# sch_cm4.net
KiCad netlist of a schematic drawn in Altium Designer
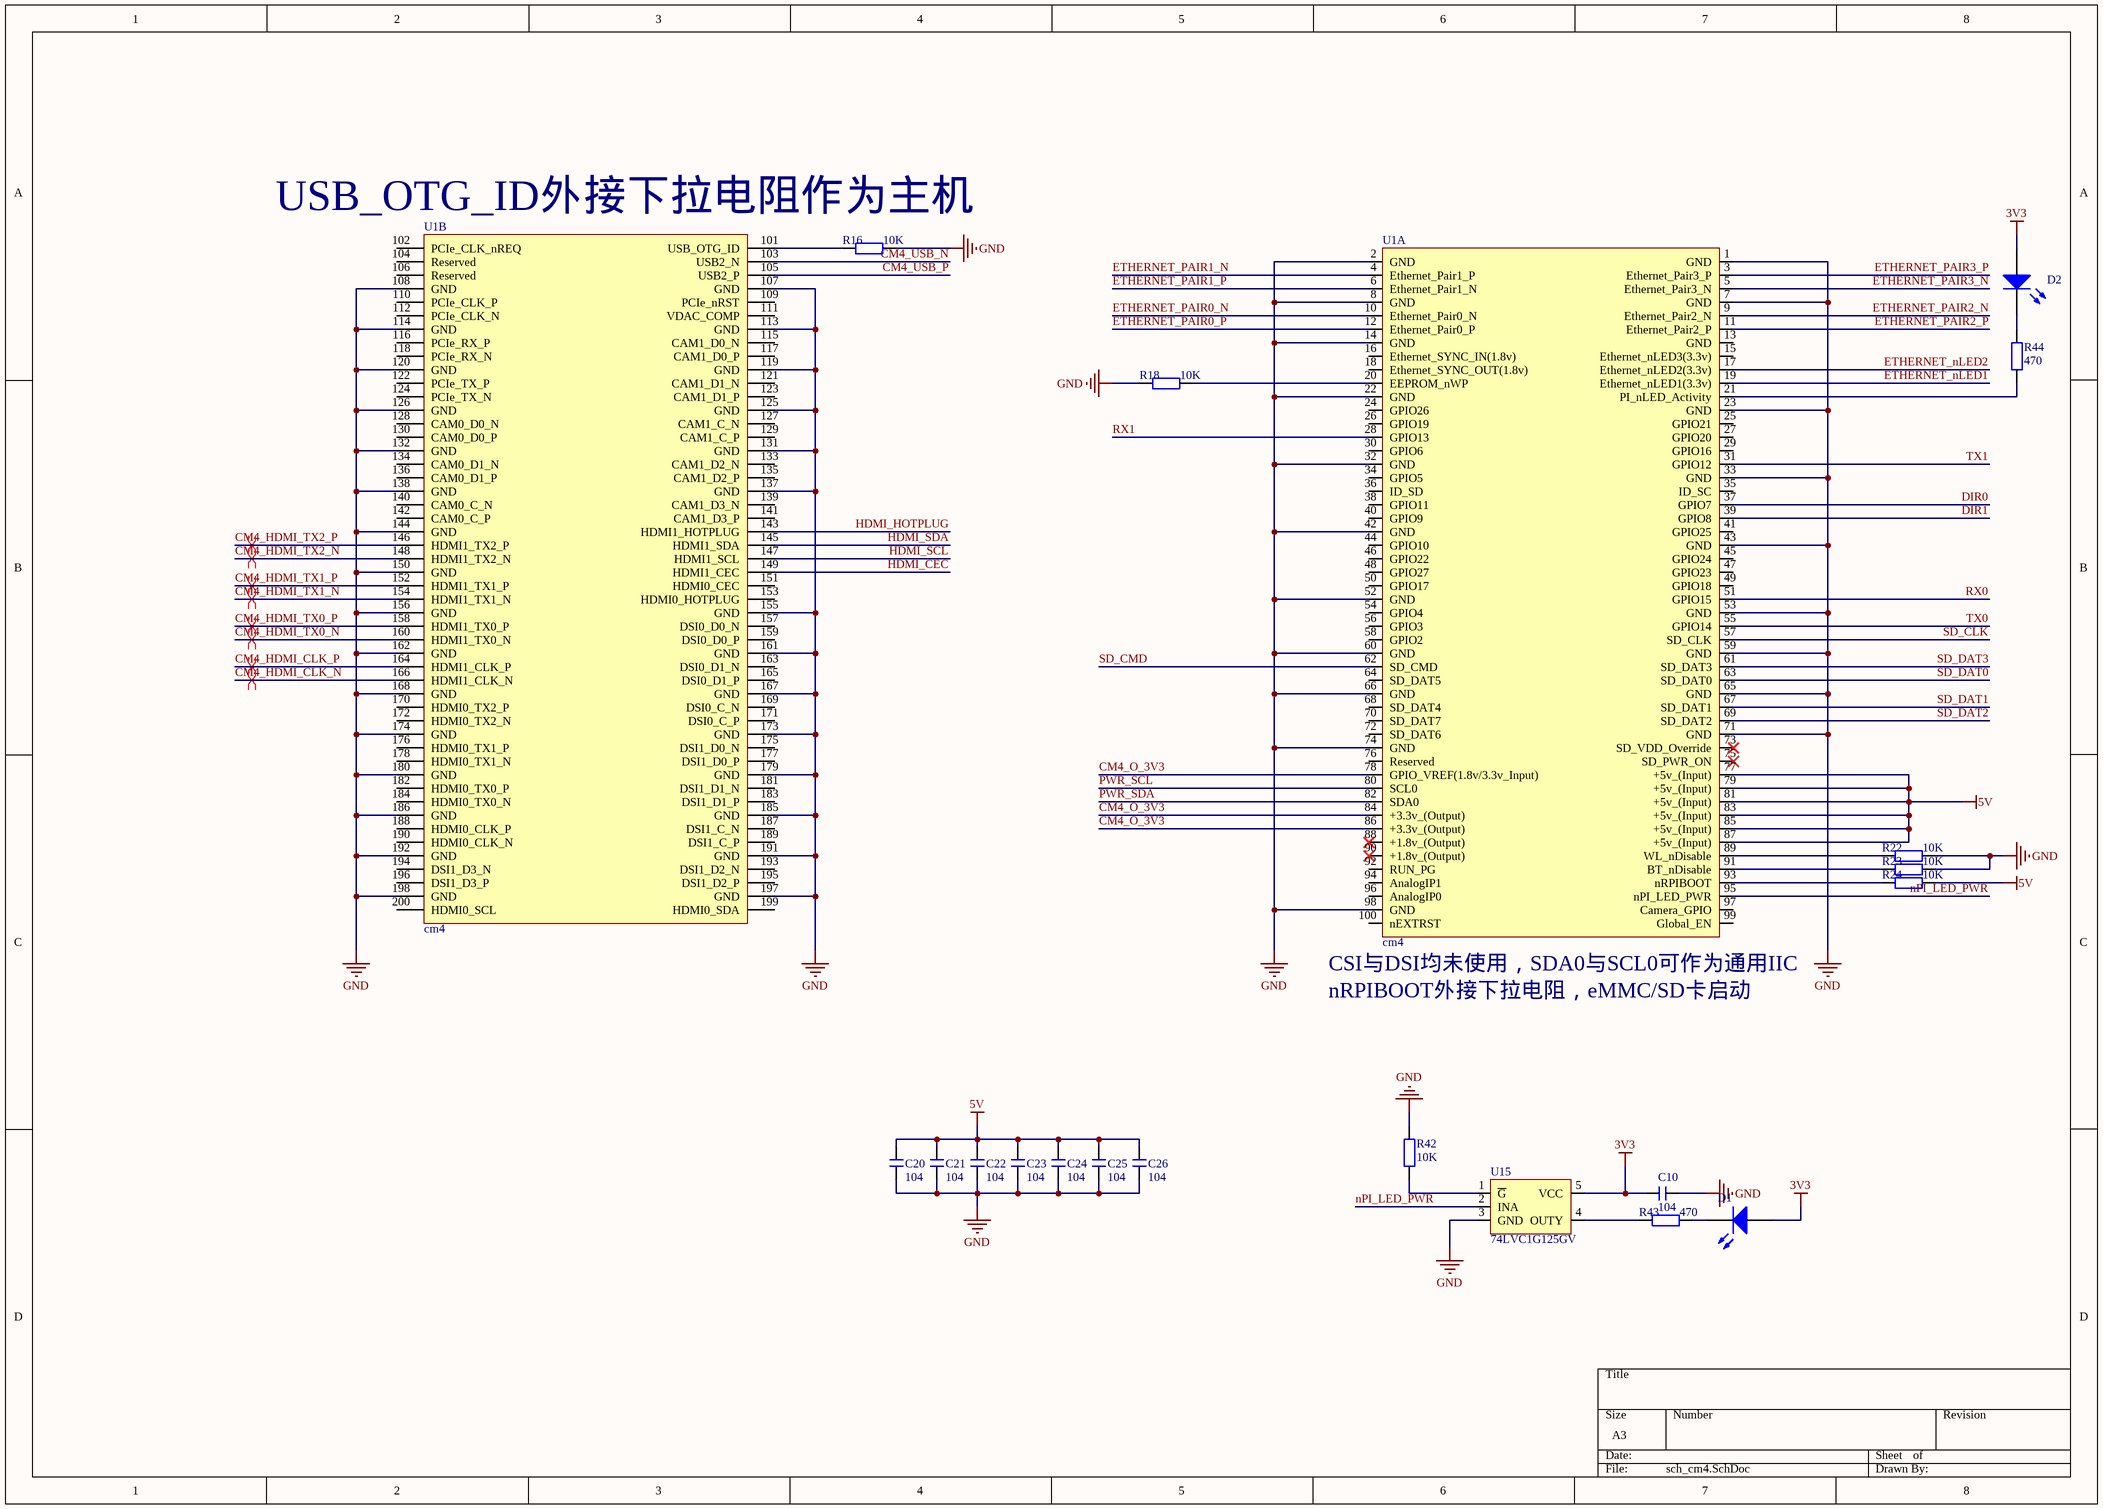
[diagram p0: sch_cm4.SchDoc]

(export (version "E")
  (design (tool "Eeschema 10.0.6"))
  (components
    (comp (ref "C10")
      (value "104")
      (footprint "C 0402_L")
      (description "贴片电容")
      (libsource (lib "0.1 - 电阻-电容-电感") (part "C"))
    )
    (comp (ref "C20")
      (value "104")
      (footprint "C 0402_L")
      (description "贴片电容")
      (libsource (lib "0.1 - 电阻-电容-电感") (part "C"))
    )
    (comp (ref "C21")
      (value "104")
      (footprint "C 0402_L")
      (description "贴片电容")
      (libsource (lib "0.1 - 电阻-电容-电感") (part "C"))
    )
    (comp (ref "C22")
      (value "104")
      (footprint "C 0402_L")
      (description "贴片电容")
      (libsource (lib "0.1 - 电阻-电容-电感") (part "C"))
    )
    (comp (ref "C23")
      (value "104")
      (footprint "C 0402_L")
      (description "贴片电容")
      (libsource (lib "0.1 - 电阻-电容-电感") (part "C"))
    )
    (comp (ref "C24")
      (value "104")
      (footprint "C 0402_L")
      (description "贴片电容")
      (libsource (lib "0.1 - 电阻-电容-电感") (part "C"))
    )
    (comp (ref "C25")
      (value "104")
      (footprint "C 0402_L")
      (description "贴片电容")
      (libsource (lib "0.1 - 电阻-电容-电感") (part "C"))
    )
    (comp (ref "C26")
      (value "104")
      (footprint "C 0402_L")
      (description "贴片电容")
      (libsource (lib "0.1 - 电阻-电容-电感") (part "C"))
    )
    (comp (ref "D1")
      (value "Light-Emitting Diode")
      (libsource (lib "Simulation Generic Components") (part "LED"))
    )
    (comp (ref "D2")
      (value "Light-Emitting Diode")
      (libsource (lib "Simulation Generic Components") (part "LED"))
    )
    (comp (ref "R16")
      (value "10K")
      (footprint "R 0805_L")
      (description "贴片电阻")
      (fields (field (name "版权归属") "来自淘宝 ID：黄晶宝石"))
      (libsource (lib "0.1 - 电阻-电容-电感") (part "R"))
    )
    (comp (ref "R18")
      (value "10K")
      (footprint "R 0805_L")
      (description "贴片电阻")
      (fields (field (name "版权归属") "来自淘宝 ID：黄晶宝石"))
      (libsource (lib "0.1 - 电阻-电容-电感") (part "R"))
    )
    (comp (ref "R22")
      (value "10K")
      (footprint "R 0805_L")
      (description "贴片电阻")
      (fields (field (name "版权归属") "来自淘宝 ID：黄晶宝石"))
      (libsource (lib "0.1 - 电阻-电容-电感") (part "R"))
    )
    (comp (ref "R23")
      (value "10K")
      (footprint "R 0805_L")
      (description "贴片电阻")
      (fields (field (name "版权归属") "来自淘宝 ID：黄晶宝石"))
      (libsource (lib "0.1 - 电阻-电容-电感") (part "R"))
    )
    (comp (ref "R24")
      (value "10K")
      (footprint "R 0805_L")
      (description "贴片电阻")
      (fields (field (name "版权归属") "来自淘宝 ID：黄晶宝石"))
      (libsource (lib "0.1 - 电阻-电容-电感") (part "R"))
    )
    (comp (ref "R42")
      (value "10K")
      (footprint "R 0805_L")
      (description "贴片电阻")
      (fields (field (name "版权归属") "来自淘宝 ID：黄晶宝石"))
      (libsource (lib "0.1 - 电阻-电容-电感") (part "R"))
    )
    (comp (ref "R43")
      (value "470")
      (footprint "R 0805_L")
      (description "贴片电阻")
      (fields (field (name "版权归属") "来自淘宝 ID：黄晶宝石"))
      (libsource (lib "0.1 - 电阻-电容-电感") (part "R"))
    )
    (comp (ref "R44")
      (value "470")
      (footprint "R 0805_L")
      (description "贴片电阻")
      (fields (field (name "版权归属") "来自淘宝 ID：黄晶宝石"))
      (libsource (lib "0.1 - 电阻-电容-电感") (part "R"))
    )
    (comp (ref "U1")
      (value "cm4")
      (footprint "Pi-cm4")
      (description "ComputerModule4")
      (libsource (lib "schlib_cm4") (part "ComputerModule4"))
    )
    (comp (ref "U15")
      (value "74LVC1G125GV")
      (footprint "SOT-23-5_L2.9-W1.6-P0.95-LS2.8-BR")
      (description "缓冲器")
      (libsource (lib "schlib_cm4") (part "74LVC1G125GV"))
    )
  )
  (nets
    (net (code "1") (name "/CM4_HDMI_CLK_N") (class "Default")
      (node (ref "U1") (pin "166") (pinfunction "HDMI1_CLK_N_166") (pintype "passive"))
    )
    (net (code "2") (name "/CM4_HDMI_CLK_P") (class "Default")
      (node (ref "U1") (pin "164") (pinfunction "HDMI1_CLK_P_164") (pintype "passive"))
    )
    (net (code "3") (name "/CM4_HDMI_TX0_N") (class "Default")
      (node (ref "U1") (pin "160") (pinfunction "HDMI1_TX0_N_160") (pintype "passive"))
    )
    (net (code "4") (name "/CM4_HDMI_TX0_P") (class "Default")
      (node (ref "U1") (pin "158") (pinfunction "HDMI1_TX0_P_158") (pintype "passive"))
    )
    (net (code "5") (name "/CM4_HDMI_TX1_N") (class "Default")
      (node (ref "U1") (pin "154") (pinfunction "HDMI1_TX1_N_154") (pintype "passive"))
    )
    (net (code "6") (name "/CM4_HDMI_TX1_P") (class "Default")
      (node (ref "U1") (pin "152") (pinfunction "HDMI1_TX1_P_152") (pintype "passive"))
    )
    (net (code "7") (name "/CM4_HDMI_TX2_N") (class "Default")
      (node (ref "U1") (pin "148") (pinfunction "HDMI1_TX2_N_148") (pintype "passive"))
    )
    (net (code "8") (name "/CM4_HDMI_TX2_P") (class "Default")
      (node (ref "U1") (pin "146") (pinfunction "HDMI1_TX2_P_146") (pintype "passive"))
    )
    (net (code "9") (name "/CM4_O_3V3") (class "Default")
      (node (ref "U1") (pin "78") (pinfunction "GPIO_VREF(1.8v/3.3v_Input)_78") (pintype "passive"))
      (node (ref "U1") (pin "84") (pinfunction "+3.3v_(Output)_84") (pintype "passive"))
      (node (ref "U1") (pin "86") (pinfunction "+3.3v_(Output)_86") (pintype "passive"))
    )
    (net (code "10") (name "/CM4_USB_N") (class "Default")
      (node (ref "U1") (pin "103") (pinfunction "USB2_N_103") (pintype "passive"))
    )
    (net (code "11") (name "/CM4_USB_P") (class "Default")
      (node (ref "U1") (pin "105") (pinfunction "USB2_P_105") (pintype "passive"))
    )
    (net (code "12") (name "/DIR0") (class "Default")
      (node (ref "U1") (pin "37") (pinfunction "GPIO7_37") (pintype "passive"))
    )
    (net (code "13") (name "/DIR1") (class "Default")
      (node (ref "U1") (pin "39") (pinfunction "GPIO8_39") (pintype "passive"))
    )
    (net (code "14") (name "/ETHERNET_PAIR0_N") (class "Default")
      (node (ref "U1") (pin "10") (pinfunction "Ethernet_Pair0_N_10") (pintype "passive"))
    )
    (net (code "15") (name "/ETHERNET_PAIR0_P") (class "Default")
      (node (ref "U1") (pin "12") (pinfunction "Ethernet_Pair0_P_12") (pintype "passive"))
    )
    (net (code "16") (name "/ETHERNET_PAIR1_N") (class "Default")
      (node (ref "U1") (pin "4") (pinfunction "Ethernet_Pair1_P_4") (pintype "passive"))
    )
    (net (code "17") (name "/ETHERNET_PAIR1_P") (class "Default")
      (node (ref "U1") (pin "6") (pinfunction "Ethernet_Pair1_N_6") (pintype "passive"))
    )
    (net (code "18") (name "/ETHERNET_PAIR2_N") (class "Default")
      (node (ref "U1") (pin "9") (pinfunction "Ethernet_Pair2_N_9") (pintype "passive"))
    )
    (net (code "19") (name "/ETHERNET_PAIR2_P") (class "Default")
      (node (ref "U1") (pin "11") (pinfunction "Ethernet_Pair2_P_11") (pintype "passive"))
    )
    (net (code "20") (name "/ETHERNET_PAIR3_N") (class "Default")
      (node (ref "U1") (pin "5") (pinfunction "Ethernet_Pair3_N_5") (pintype "passive"))
    )
    (net (code "21") (name "/ETHERNET_PAIR3_P") (class "Default")
      (node (ref "U1") (pin "3") (pinfunction "Ethernet_Pair3_P_3") (pintype "passive"))
    )
    (net (code "22") (name "/ETHERNET_nLED1") (class "Default")
      (node (ref "U1") (pin "19") (pinfunction "Ethernet_nLED1(3.3v)_19") (pintype "passive"))
    )
    (net (code "23") (name "/ETHERNET_nLED2") (class "Default")
      (node (ref "U1") (pin "17") (pinfunction "Ethernet_nLED2(3.3v)_17") (pintype "passive"))
    )
    (net (code "24") (name "/HDMI_CEC") (class "Default")
      (node (ref "U1") (pin "149") (pinfunction "HDMI1_CEC_149") (pintype "passive"))
    )
    (net (code "25") (name "/HDMI_HOTPLUG") (class "Default")
      (node (ref "U1") (pin "143") (pinfunction "HDMI1_HOTPLUG_143") (pintype "passive"))
    )
    (net (code "26") (name "/HDMI_SCL") (class "Default")
      (node (ref "U1") (pin "147") (pinfunction "HDMI1_SCL_147") (pintype "passive"))
    )
    (net (code "27") (name "/HDMI_SDA") (class "Default")
      (node (ref "U1") (pin "145") (pinfunction "HDMI1_SDA_145") (pintype "passive"))
    )
    (net (code "28") (name "/PWR_SCL") (class "Default")
      (node (ref "U1") (pin "80") (pinfunction "SCL0_80") (pintype "passive"))
    )
    (net (code "29") (name "/PWR_SDA") (class "Default")
      (node (ref "U1") (pin "82") (pinfunction "SDA0_82") (pintype "passive"))
    )
    (net (code "30") (name "/RX0") (class "Default")
      (node (ref "U1") (pin "51") (pinfunction "GPIO15_51") (pintype "passive"))
    )
    (net (code "31") (name "/RX1") (class "Default")
      (node (ref "U1") (pin "28") (pinfunction "GPIO13_28") (pintype "passive"))
    )
    (net (code "32") (name "/SD_CLK") (class "Default")
      (node (ref "U1") (pin "57") (pinfunction "SD_CLK_57") (pintype "passive"))
    )
    (net (code "33") (name "/SD_CMD") (class "Default")
      (node (ref "U1") (pin "62") (pinfunction "SD_CMD_62") (pintype "passive"))
    )
    (net (code "34") (name "/SD_DAT0") (class "Default")
      (node (ref "U1") (pin "63") (pinfunction "SD_DAT0_63") (pintype "passive"))
    )
    (net (code "35") (name "/SD_DAT1") (class "Default")
      (node (ref "U1") (pin "67") (pinfunction "SD_DAT1_67") (pintype "passive"))
    )
    (net (code "36") (name "/SD_DAT2") (class "Default")
      (node (ref "U1") (pin "69") (pinfunction "SD_DAT2_69") (pintype "passive"))
    )
    (net (code "37") (name "/SD_DAT3") (class "Default")
      (node (ref "U1") (pin "61") (pinfunction "SD_DAT3_61") (pintype "passive"))
    )
    (net (code "38") (name "/TX0") (class "Default")
      (node (ref "U1") (pin "55") (pinfunction "GPIO14_55") (pintype "passive"))
    )
    (net (code "39") (name "/TX1") (class "Default")
      (node (ref "U1") (pin "31") (pinfunction "GPIO12_31") (pintype "passive"))
    )
    (net (code "40") (name "/nPI_LED_PWR") (class "Default")
      (node (ref "U1") (pin "95") (pinfunction "nPI_LED_PWR_95") (pintype "passive"))
      (node (ref "U15") (pin "2") (pinfunction "INA_2") (pintype "passive"))
    )
    (net (code "41") (name "3V3") (class "Default")
      (node (ref "C10") (pin "2") (pinfunction "2_2") (pintype "passive"))
      (node (ref "D1") (pin "1") (pinfunction "A_1") (pintype "passive"))
      (node (ref "D2") (pin "1") (pinfunction "A_1") (pintype "passive"))
      (node (ref "U15") (pin "5") (pinfunction "VCC_5") (pintype "passive"))
    )
    (net (code "42") (name "5V") (class "Default")
      (node (ref "C20") (pin "2") (pinfunction "2_2") (pintype "passive"))
      (node (ref "C21") (pin "2") (pinfunction "2_2") (pintype "passive"))
      (node (ref "C22") (pin "2") (pinfunction "2_2") (pintype "passive"))
      (node (ref "C23") (pin "2") (pinfunction "2_2") (pintype "passive"))
      (node (ref "C24") (pin "2") (pinfunction "2_2") (pintype "passive"))
      (node (ref "C25") (pin "2") (pinfunction "2_2") (pintype "passive"))
      (node (ref "C26") (pin "2") (pinfunction "2_2") (pintype "passive"))
      (node (ref "R24") (pin "2") (pinfunction "2_2") (pintype "passive"))
      (node (ref "U1") (pin "77") (pinfunction "+5v_(Input)_77") (pintype "passive"))
      (node (ref "U1") (pin "79") (pinfunction "+5v_(Input)_79") (pintype "passive"))
      (node (ref "U1") (pin "81") (pinfunction "+5v_(Input)_81") (pintype "passive"))
      (node (ref "U1") (pin "83") (pinfunction "+5v_(Input)_83") (pintype "passive"))
      (node (ref "U1") (pin "85") (pinfunction "+5v_(Input)_85") (pintype "passive"))
      (node (ref "U1") (pin "87") (pinfunction "+5v_(Input)_87") (pintype "passive"))
    )
    (net (code "43") (name "GND") (class "Default")
      (node (ref "C10") (pin "1") (pinfunction "1_1") (pintype "passive"))
      (node (ref "C20") (pin "1") (pinfunction "1_1") (pintype "passive"))
      (node (ref "C21") (pin "1") (pinfunction "1_1") (pintype "passive"))
      (node (ref "C22") (pin "1") (pinfunction "1_1") (pintype "passive"))
      (node (ref "C23") (pin "1") (pinfunction "1_1") (pintype "passive"))
      (node (ref "C24") (pin "1") (pinfunction "1_1") (pintype "passive"))
      (node (ref "C25") (pin "1") (pinfunction "1_1") (pintype "passive"))
      (node (ref "C26") (pin "1") (pinfunction "1_1") (pintype "passive"))
      (node (ref "R16") (pin "2") (pinfunction "2_2") (pintype "passive"))
      (node (ref "R18") (pin "1") (pinfunction "1_1") (pintype "passive"))
      (node (ref "R22") (pin "2") (pinfunction "2_2") (pintype "passive"))
      (node (ref "R23") (pin "2") (pinfunction "2_2") (pintype "passive"))
      (node (ref "R42") (pin "1") (pinfunction "1_1") (pintype "passive"))
      (node (ref "U1") (pin "1") (pinfunction "GND_1") (pintype "passive"))
      (node (ref "U1") (pin "107") (pinfunction "GND_107") (pintype "passive"))
      (node (ref "U1") (pin "108") (pinfunction "GND_108") (pintype "passive"))
      (node (ref "U1") (pin "113") (pinfunction "GND_113") (pintype "passive"))
      (node (ref "U1") (pin "114") (pinfunction "GND_114") (pintype "passive"))
      (node (ref "U1") (pin "119") (pinfunction "GND_119") (pintype "passive"))
      (node (ref "U1") (pin "120") (pinfunction "GND_120") (pintype "passive"))
      (node (ref "U1") (pin "125") (pinfunction "GND_125") (pintype "passive"))
      (node (ref "U1") (pin "126") (pinfunction "GND_126") (pintype "passive"))
      (node (ref "U1") (pin "131") (pinfunction "GND_131") (pintype "passive"))
      (node (ref "U1") (pin "132") (pinfunction "GND_132") (pintype "passive"))
      (node (ref "U1") (pin "137") (pinfunction "GND_137") (pintype "passive"))
      (node (ref "U1") (pin "138") (pinfunction "GND_138") (pintype "passive"))
      (node (ref "U1") (pin "14") (pinfunction "GND_14") (pintype "passive"))
      (node (ref "U1") (pin "144") (pinfunction "GND_144") (pintype "passive"))
      (node (ref "U1") (pin "150") (pinfunction "GND_150") (pintype "passive"))
      (node (ref "U1") (pin "155") (pinfunction "GND_155") (pintype "passive"))
      (node (ref "U1") (pin "156") (pinfunction "GND_156") (pintype "passive"))
      (node (ref "U1") (pin "161") (pinfunction "GND_161") (pintype "passive"))
      (node (ref "U1") (pin "162") (pinfunction "GND_162") (pintype "passive"))
      (node (ref "U1") (pin "167") (pinfunction "GND_167") (pintype "passive"))
      (node (ref "U1") (pin "168") (pinfunction "GND_168") (pintype "passive"))
      (node (ref "U1") (pin "173") (pinfunction "GND_173") (pintype "passive"))
      (node (ref "U1") (pin "174") (pinfunction "GND_174") (pintype "passive"))
      (node (ref "U1") (pin "179") (pinfunction "GND_179") (pintype "passive"))
      (node (ref "U1") (pin "180") (pinfunction "GND_180") (pintype "passive"))
      (node (ref "U1") (pin "185") (pinfunction "GND_185") (pintype "passive"))
      (node (ref "U1") (pin "186") (pinfunction "GND_186") (pintype "passive"))
      (node (ref "U1") (pin "191") (pinfunction "GND_191") (pintype "passive"))
      (node (ref "U1") (pin "192") (pinfunction "GND_192") (pintype "passive"))
      (node (ref "U1") (pin "197") (pinfunction "GND_197") (pintype "passive"))
      (node (ref "U1") (pin "198") (pinfunction "GND_198") (pintype "passive"))
      (node (ref "U1") (pin "2") (pinfunction "GND_2") (pintype "passive"))
      (node (ref "U1") (pin "22") (pinfunction "GND_22") (pintype "passive"))
      (node (ref "U1") (pin "23") (pinfunction "GND_23") (pintype "passive"))
      (node (ref "U1") (pin "32") (pinfunction "GND_32") (pintype "passive"))
      (node (ref "U1") (pin "33") (pinfunction "GND_33") (pintype "passive"))
      (node (ref "U1") (pin "42") (pinfunction "GND_42") (pintype "passive"))
      (node (ref "U1") (pin "43") (pinfunction "GND_43") (pintype "passive"))
      (node (ref "U1") (pin "52") (pinfunction "GND_52") (pintype "passive"))
      (node (ref "U1") (pin "53") (pinfunction "GND_53") (pintype "passive"))
      (node (ref "U1") (pin "59") (pinfunction "GND_59") (pintype "passive"))
      (node (ref "U1") (pin "60") (pinfunction "GND_60") (pintype "passive"))
      (node (ref "U1") (pin "65") (pinfunction "GND_65") (pintype "passive"))
      (node (ref "U1") (pin "66") (pinfunction "GND_66") (pintype "passive"))
      (node (ref "U1") (pin "7") (pinfunction "GND_7") (pintype "passive"))
      (node (ref "U1") (pin "71") (pinfunction "GND_71") (pintype "passive"))
      (node (ref "U1") (pin "74") (pinfunction "GND_74") (pintype "passive"))
      (node (ref "U1") (pin "8") (pinfunction "GND_8") (pintype "passive"))
      (node (ref "U1") (pin "98") (pinfunction "GND_98") (pintype "passive"))
      (node (ref "U15") (pin "3") (pinfunction "GND_3") (pintype "passive"))
    )
    (net (code "44") (name "Net-(D1-K)") (class "Default")
      (node (ref "D1") (pin "2") (pinfunction "K_2") (pintype "passive"))
      (node (ref "R43") (pin "2") (pinfunction "2_2") (pintype "passive"))
    )
    (net (code "45") (name "Net-(D2-K)") (class "Default")
      (node (ref "D2") (pin "2") (pinfunction "K_2") (pintype "passive"))
      (node (ref "R44") (pin "2") (pinfunction "2_2") (pintype "passive"))
    )
    (net (code "46") (name "Net-(U1A-BT_nDisable)") (class "Default")
      (node (ref "R23") (pin "1") (pinfunction "1_1") (pintype "passive"))
      (node (ref "U1") (pin "91") (pinfunction "BT_nDisable_91") (pintype "passive"))
    )
    (net (code "47") (name "Net-(U1A-EEPROM_nWP)") (class "Default")
      (node (ref "R18") (pin "2") (pinfunction "2_2") (pintype "passive"))
      (node (ref "U1") (pin "20") (pinfunction "EEPROM_nWP_20") (pintype "passive"))
    )
    (net (code "48") (name "Net-(U1A-PI_nLED_Activity)") (class "Default")
      (node (ref "R44") (pin "1") (pinfunction "1_1") (pintype "passive"))
      (node (ref "U1") (pin "21") (pinfunction "PI_nLED_Activity_21") (pintype "passive"))
    )
    (net (code "49") (name "Net-(U1A-WL_nDisable)") (class "Default")
      (node (ref "R22") (pin "1") (pinfunction "1_1") (pintype "passive"))
      (node (ref "U1") (pin "89") (pinfunction "WL_nDisable_89") (pintype "passive"))
    )
    (net (code "50") (name "Net-(U1A-nRPIBOOT)") (class "Default")
      (node (ref "R24") (pin "1") (pinfunction "1_1") (pintype "passive"))
      (node (ref "U1") (pin "93") (pinfunction "nRPIBOOT_93") (pintype "passive"))
    )
    (net (code "51") (name "Net-(U1B-USB_OTG_ID)") (class "Default")
      (node (ref "R16") (pin "1") (pinfunction "1_1") (pintype "passive"))
      (node (ref "U1") (pin "101") (pinfunction "USB_OTG_ID_101") (pintype "passive"))
    )
    (net (code "52") (name "Net-(U15-OUTY)") (class "Default")
      (node (ref "R43") (pin "1") (pinfunction "1_1") (pintype "passive"))
      (node (ref "U15") (pin "4") (pinfunction "OUTY_4") (pintype "passive"))
    )
    (net (code "53") (name "Net-(U15-~{G})") (class "Default")
      (node (ref "R42") (pin "2") (pinfunction "2_2") (pintype "passive"))
      (node (ref "U15") (pin "1") (pinfunction "~{G}_1") (pintype "passive"))
    )
    (net (code "54") (name "unconnected-(U1A-+1.8v_(Output)-Pad88)") (class "Default")
      (node (ref "U1") (pin "88") (pinfunction "+1.8v_(Output)_88") (pintype "passive+no_connect"))
    )
    (net (code "55") (name "unconnected-(U1A-+1.8v_(Output)-Pad90)") (class "Default")
      (node (ref "U1") (pin "90") (pinfunction "+1.8v_(Output)_90") (pintype "passive+no_connect"))
    )
    (net (code "56") (name "unconnected-(U1A-AnalogIP0-Pad96)") (class "Default")
      (node (ref "U1") (pin "96") (pinfunction "AnalogIP0_96") (pintype "passive"))
    )
    (net (code "57") (name "unconnected-(U1A-AnalogIP1-Pad94)") (class "Default")
      (node (ref "U1") (pin "94") (pinfunction "AnalogIP1_94") (pintype "passive"))
    )
    (net (code "58") (name "unconnected-(U1A-Camera_GPIO-Pad97)") (class "Default")
      (node (ref "U1") (pin "97") (pinfunction "Camera_GPIO_97") (pintype "passive"))
    )
    (net (code "59") (name "unconnected-(U1A-Ethernet_SYNC_IN(1.8v)-Pad16)") (class "Default")
      (node (ref "U1") (pin "16") (pinfunction "Ethernet_SYNC_IN(1.8v)_16") (pintype "passive"))
    )
    (net (code "60") (name "unconnected-(U1A-Ethernet_SYNC_OUT(1.8v)-Pad18)") (class "Default")
      (node (ref "U1") (pin "18") (pinfunction "Ethernet_SYNC_OUT(1.8v)_18") (pintype "passive"))
    )
    (net (code "61") (name "unconnected-(U1A-Ethernet_nLED3(3.3v)-Pad15)") (class "Default")
      (node (ref "U1") (pin "15") (pinfunction "Ethernet_nLED3(3.3v)_15") (pintype "passive"))
    )
    (net (code "62") (name "unconnected-(U1A-GND-Pad13)") (class "Default")
      (node (ref "U1") (pin "13") (pinfunction "GND_13") (pintype "passive"))
    )
    (net (code "63") (name "unconnected-(U1A-GPIO2-Pad58)") (class "Default")
      (node (ref "U1") (pin "58") (pinfunction "GPIO2_58") (pintype "passive"))
    )
    (net (code "64") (name "unconnected-(U1A-GPIO3-Pad56)") (class "Default")
      (node (ref "U1") (pin "56") (pinfunction "GPIO3_56") (pintype "passive"))
    )
    (net (code "65") (name "unconnected-(U1A-GPIO4-Pad54)") (class "Default")
      (node (ref "U1") (pin "54") (pinfunction "GPIO4_54") (pintype "passive"))
    )
    (net (code "66") (name "unconnected-(U1A-GPIO5-Pad34)") (class "Default")
      (node (ref "U1") (pin "34") (pinfunction "GPIO5_34") (pintype "passive"))
    )
    (net (code "67") (name "unconnected-(U1A-GPIO6-Pad30)") (class "Default")
      (node (ref "U1") (pin "30") (pinfunction "GPIO6_30") (pintype "passive"))
    )
    (net (code "68") (name "unconnected-(U1A-GPIO9-Pad40)") (class "Default")
      (node (ref "U1") (pin "40") (pinfunction "GPIO9_40") (pintype "passive"))
    )
    (net (code "69") (name "unconnected-(U1A-GPIO10-Pad44)") (class "Default")
      (node (ref "U1") (pin "44") (pinfunction "GPIO10_44") (pintype "passive"))
    )
    (net (code "70") (name "unconnected-(U1A-GPIO11-Pad38)") (class "Default")
      (node (ref "U1") (pin "38") (pinfunction "GPIO11_38") (pintype "passive"))
    )
    (net (code "71") (name "unconnected-(U1A-GPIO16-Pad29)") (class "Default")
      (node (ref "U1") (pin "29") (pinfunction "GPIO16_29") (pintype "passive"))
    )
    (net (code "72") (name "unconnected-(U1A-GPIO17-Pad50)") (class "Default")
      (node (ref "U1") (pin "50") (pinfunction "GPIO17_50") (pintype "passive"))
    )
    (net (code "73") (name "unconnected-(U1A-GPIO18-Pad49)") (class "Default")
      (node (ref "U1") (pin "49") (pinfunction "GPIO18_49") (pintype "passive"))
    )
    (net (code "74") (name "unconnected-(U1A-GPIO19-Pad26)") (class "Default")
      (node (ref "U1") (pin "26") (pinfunction "GPIO19_26") (pintype "passive"))
    )
    (net (code "75") (name "unconnected-(U1A-GPIO20-Pad27)") (class "Default")
      (node (ref "U1") (pin "27") (pinfunction "GPIO20_27") (pintype "passive"))
    )
    (net (code "76") (name "unconnected-(U1A-GPIO21-Pad25)") (class "Default")
      (node (ref "U1") (pin "25") (pinfunction "GPIO21_25") (pintype "passive"))
    )
    (net (code "77") (name "unconnected-(U1A-GPIO22-Pad46)") (class "Default")
      (node (ref "U1") (pin "46") (pinfunction "GPIO22_46") (pintype "passive"))
    )
    (net (code "78") (name "unconnected-(U1A-GPIO23-Pad47)") (class "Default")
      (node (ref "U1") (pin "47") (pinfunction "GPIO23_47") (pintype "passive"))
    )
    (net (code "79") (name "unconnected-(U1A-GPIO24-Pad45)") (class "Default")
      (node (ref "U1") (pin "45") (pinfunction "GPIO24_45") (pintype "passive"))
    )
    (net (code "80") (name "unconnected-(U1A-GPIO25-Pad41)") (class "Default")
      (node (ref "U1") (pin "41") (pinfunction "GPIO25_41") (pintype "passive"))
    )
    (net (code "81") (name "unconnected-(U1A-GPIO26-Pad24)") (class "Default")
      (node (ref "U1") (pin "24") (pinfunction "GPIO26_24") (pintype "passive"))
    )
    (net (code "82") (name "unconnected-(U1A-GPIO27-Pad48)") (class "Default")
      (node (ref "U1") (pin "48") (pinfunction "GPIO27_48") (pintype "passive"))
    )
    (net (code "83") (name "unconnected-(U1A-Global_EN-Pad99)") (class "Default")
      (node (ref "U1") (pin "99") (pinfunction "Global_EN_99") (pintype "passive"))
    )
    (net (code "84") (name "unconnected-(U1A-ID_SC-Pad35)") (class "Default")
      (node (ref "U1") (pin "35") (pinfunction "ID_SC_35") (pintype "passive"))
    )
    (net (code "85") (name "unconnected-(U1A-ID_SD-Pad36)") (class "Default")
      (node (ref "U1") (pin "36") (pinfunction "ID_SD_36") (pintype "passive"))
    )
    (net (code "86") (name "unconnected-(U1A-RUN_PG-Pad92)") (class "Default")
      (node (ref "U1") (pin "92") (pinfunction "RUN_PG_92") (pintype "passive"))
    )
    (net (code "87") (name "unconnected-(U1A-Reserved-Pad76)") (class "Default")
      (node (ref "U1") (pin "76") (pinfunction "Reserved_76") (pintype "passive"))
    )
    (net (code "88") (name "unconnected-(U1A-SD_DAT4-Pad68)") (class "Default")
      (node (ref "U1") (pin "68") (pinfunction "SD_DAT4_68") (pintype "passive"))
    )
    (net (code "89") (name "unconnected-(U1A-SD_DAT5-Pad64)") (class "Default")
      (node (ref "U1") (pin "64") (pinfunction "SD_DAT5_64") (pintype "passive"))
    )
    (net (code "90") (name "unconnected-(U1A-SD_DAT6-Pad72)") (class "Default")
      (node (ref "U1") (pin "72") (pinfunction "SD_DAT6_72") (pintype "passive"))
    )
    (net (code "91") (name "unconnected-(U1A-SD_DAT7-Pad70)") (class "Default")
      (node (ref "U1") (pin "70") (pinfunction "SD_DAT7_70") (pintype "passive"))
    )
    (net (code "92") (name "unconnected-(U1A-SD_PWR_ON-Pad75)") (class "Default")
      (node (ref "U1") (pin "75") (pinfunction "SD_PWR_ON_75") (pintype "passive+no_connect"))
    )
    (net (code "93") (name "unconnected-(U1A-SD_VDD_Override-Pad73)") (class "Default")
      (node (ref "U1") (pin "73") (pinfunction "SD_VDD_Override_73") (pintype "passive+no_connect"))
    )
    (net (code "94") (name "unconnected-(U1A-nEXTRST-Pad100)") (class "Default")
      (node (ref "U1") (pin "100") (pinfunction "nEXTRST_100") (pintype "passive"))
    )
    (net (code "95") (name "unconnected-(U1B-CAM0_C_N-Pad140)") (class "Default")
      (node (ref "U1") (pin "140") (pinfunction "CAM0_C_N_140") (pintype "passive"))
    )
    (net (code "96") (name "unconnected-(U1B-CAM0_C_P-Pad142)") (class "Default")
      (node (ref "U1") (pin "142") (pinfunction "CAM0_C_P_142") (pintype "passive"))
    )
    (net (code "97") (name "unconnected-(U1B-CAM0_D0_N-Pad128)") (class "Default")
      (node (ref "U1") (pin "128") (pinfunction "CAM0_D0_N_128") (pintype "passive"))
    )
    (net (code "98") (name "unconnected-(U1B-CAM0_D0_P-Pad130)") (class "Default")
      (node (ref "U1") (pin "130") (pinfunction "CAM0_D0_P_130") (pintype "passive"))
    )
    (net (code "99") (name "unconnected-(U1B-CAM0_D1_N-Pad134)") (class "Default")
      (node (ref "U1") (pin "134") (pinfunction "CAM0_D1_N_134") (pintype "passive"))
    )
    (net (code "100") (name "unconnected-(U1B-CAM0_D1_P-Pad136)") (class "Default")
      (node (ref "U1") (pin "136") (pinfunction "CAM0_D1_P_136") (pintype "passive"))
    )
    (net (code "101") (name "unconnected-(U1B-CAM1_C_N-Pad127)") (class "Default")
      (node (ref "U1") (pin "127") (pinfunction "CAM1_C_N_127") (pintype "passive"))
    )
    (net (code "102") (name "unconnected-(U1B-CAM1_C_P-Pad129)") (class "Default")
      (node (ref "U1") (pin "129") (pinfunction "CAM1_C_P_129") (pintype "passive"))
    )
    (net (code "103") (name "unconnected-(U1B-CAM1_D0_N-Pad115)") (class "Default")
      (node (ref "U1") (pin "115") (pinfunction "CAM1_D0_N_115") (pintype "passive"))
    )
    (net (code "104") (name "unconnected-(U1B-CAM1_D0_P-Pad117)") (class "Default")
      (node (ref "U1") (pin "117") (pinfunction "CAM1_D0_P_117") (pintype "passive"))
    )
    (net (code "105") (name "unconnected-(U1B-CAM1_D1_N-Pad121)") (class "Default")
      (node (ref "U1") (pin "121") (pinfunction "CAM1_D1_N_121") (pintype "passive"))
    )
    (net (code "106") (name "unconnected-(U1B-CAM1_D1_P-Pad123)") (class "Default")
      (node (ref "U1") (pin "123") (pinfunction "CAM1_D1_P_123") (pintype "passive"))
    )
    (net (code "107") (name "unconnected-(U1B-CAM1_D2_N-Pad133)") (class "Default")
      (node (ref "U1") (pin "133") (pinfunction "CAM1_D2_N_133") (pintype "passive"))
    )
    (net (code "108") (name "unconnected-(U1B-CAM1_D2_P-Pad135)") (class "Default")
      (node (ref "U1") (pin "135") (pinfunction "CAM1_D2_P_135") (pintype "passive"))
    )
    (net (code "109") (name "unconnected-(U1B-CAM1_D3_N-Pad139)") (class "Default")
      (node (ref "U1") (pin "139") (pinfunction "CAM1_D3_N_139") (pintype "passive"))
    )
    (net (code "110") (name "unconnected-(U1B-CAM1_D3_P-Pad141)") (class "Default")
      (node (ref "U1") (pin "141") (pinfunction "CAM1_D3_P_141") (pintype "passive"))
    )
    (net (code "111") (name "unconnected-(U1B-DSI0_C_N-Pad169)") (class "Default")
      (node (ref "U1") (pin "169") (pinfunction "DSI0_C_N_169") (pintype "passive"))
    )
    (net (code "112") (name "unconnected-(U1B-DSI0_C_P-Pad171)") (class "Default")
      (node (ref "U1") (pin "171") (pinfunction "DSI0_C_P_171") (pintype "passive"))
    )
    (net (code "113") (name "unconnected-(U1B-DSI0_D0_N-Pad157)") (class "Default")
      (node (ref "U1") (pin "157") (pinfunction "DSI0_D0_N_157") (pintype "passive"))
    )
    (net (code "114") (name "unconnected-(U1B-DSI0_D0_P-Pad159)") (class "Default")
      (node (ref "U1") (pin "159") (pinfunction "DSI0_D0_P_159") (pintype "passive"))
    )
    (net (code "115") (name "unconnected-(U1B-DSI0_D1_N-Pad163)") (class "Default")
      (node (ref "U1") (pin "163") (pinfunction "DSI0_D1_N_163") (pintype "passive"))
    )
    (net (code "116") (name "unconnected-(U1B-DSI0_D1_P-Pad165)") (class "Default")
      (node (ref "U1") (pin "165") (pinfunction "DSI0_D1_P_165") (pintype "passive"))
    )
    (net (code "117") (name "unconnected-(U1B-DSI1_C_N-Pad187)") (class "Default")
      (node (ref "U1") (pin "187") (pinfunction "DSI1_C_N_187") (pintype "passive"))
    )
    (net (code "118") (name "unconnected-(U1B-DSI1_C_P-Pad189)") (class "Default")
      (node (ref "U1") (pin "189") (pinfunction "DSI1_C_P_189") (pintype "passive"))
    )
    (net (code "119") (name "unconnected-(U1B-DSI1_D0_N-Pad175)") (class "Default")
      (node (ref "U1") (pin "175") (pinfunction "DSI1_D0_N_175") (pintype "passive"))
    )
    (net (code "120") (name "unconnected-(U1B-DSI1_D0_P-Pad177)") (class "Default")
      (node (ref "U1") (pin "177") (pinfunction "DSI1_D0_P_177") (pintype "passive"))
    )
    (net (code "121") (name "unconnected-(U1B-DSI1_D1_N-Pad181)") (class "Default")
      (node (ref "U1") (pin "181") (pinfunction "DSI1_D1_N_181") (pintype "passive"))
    )
    (net (code "122") (name "unconnected-(U1B-DSI1_D1_P-Pad183)") (class "Default")
      (node (ref "U1") (pin "183") (pinfunction "DSI1_D1_P_183") (pintype "passive"))
    )
    (net (code "123") (name "unconnected-(U1B-DSI1_D2_N-Pad193)") (class "Default")
      (node (ref "U1") (pin "193") (pinfunction "DSI1_D2_N_193") (pintype "passive"))
    )
    (net (code "124") (name "unconnected-(U1B-DSI1_D2_P-Pad195)") (class "Default")
      (node (ref "U1") (pin "195") (pinfunction "DSI1_D2_P_195") (pintype "passive"))
    )
    (net (code "125") (name "unconnected-(U1B-DSI1_D3_N-Pad194)") (class "Default")
      (node (ref "U1") (pin "194") (pinfunction "DSI1_D3_N_194") (pintype "passive"))
    )
    (net (code "126") (name "unconnected-(U1B-DSI1_D3_P-Pad196)") (class "Default")
      (node (ref "U1") (pin "196") (pinfunction "DSI1_D3_P_196") (pintype "passive"))
    )
    (net (code "127") (name "unconnected-(U1B-HDMI0_CEC-Pad151)") (class "Default")
      (node (ref "U1") (pin "151") (pinfunction "HDMI0_CEC_151") (pintype "passive"))
    )
    (net (code "128") (name "unconnected-(U1B-HDMI0_CLK_N-Pad190)") (class "Default")
      (node (ref "U1") (pin "190") (pinfunction "HDMI0_CLK_N_190") (pintype "passive"))
    )
    (net (code "129") (name "unconnected-(U1B-HDMI0_CLK_P-Pad188)") (class "Default")
      (node (ref "U1") (pin "188") (pinfunction "HDMI0_CLK_P_188") (pintype "passive"))
    )
    (net (code "130") (name "unconnected-(U1B-HDMI0_HOTPLUG-Pad153)") (class "Default")
      (node (ref "U1") (pin "153") (pinfunction "HDMI0_HOTPLUG_153") (pintype "passive"))
    )
    (net (code "131") (name "unconnected-(U1B-HDMI0_SCL-Pad200)") (class "Default")
      (node (ref "U1") (pin "200") (pinfunction "HDMI0_SCL_200") (pintype "passive"))
    )
    (net (code "132") (name "unconnected-(U1B-HDMI0_SDA-Pad199)") (class "Default")
      (node (ref "U1") (pin "199") (pinfunction "HDMI0_SDA_199") (pintype "passive"))
    )
    (net (code "133") (name "unconnected-(U1B-HDMI0_TX0_N-Pad184)") (class "Default")
      (node (ref "U1") (pin "184") (pinfunction "HDMI0_TX0_N_184") (pintype "passive"))
    )
    (net (code "134") (name "unconnected-(U1B-HDMI0_TX0_P-Pad182)") (class "Default")
      (node (ref "U1") (pin "182") (pinfunction "HDMI0_TX0_P_182") (pintype "passive"))
    )
    (net (code "135") (name "unconnected-(U1B-HDMI0_TX1_N-Pad178)") (class "Default")
      (node (ref "U1") (pin "178") (pinfunction "HDMI0_TX1_N_178") (pintype "passive"))
    )
    (net (code "136") (name "unconnected-(U1B-HDMI0_TX1_P-Pad176)") (class "Default")
      (node (ref "U1") (pin "176") (pinfunction "HDMI0_TX1_P_176") (pintype "passive"))
    )
    (net (code "137") (name "unconnected-(U1B-HDMI0_TX2_N-Pad172)") (class "Default")
      (node (ref "U1") (pin "172") (pinfunction "HDMI0_TX2_N_172") (pintype "passive"))
    )
    (net (code "138") (name "unconnected-(U1B-HDMI0_TX2_P-Pad170)") (class "Default")
      (node (ref "U1") (pin "170") (pinfunction "HDMI0_TX2_P_170") (pintype "passive"))
    )
    (net (code "139") (name "unconnected-(U1B-PCIe_CLK_N-Pad112)") (class "Default")
      (node (ref "U1") (pin "112") (pinfunction "PCIe_CLK_N_112") (pintype "passive"))
    )
    (net (code "140") (name "unconnected-(U1B-PCIe_CLK_P-Pad110)") (class "Default")
      (node (ref "U1") (pin "110") (pinfunction "PCIe_CLK_P_110") (pintype "passive"))
    )
    (net (code "141") (name "unconnected-(U1B-PCIe_CLK_nREQ-Pad102)") (class "Default")
      (node (ref "U1") (pin "102") (pinfunction "PCIe_CLK_nREQ_102") (pintype "passive"))
    )
    (net (code "142") (name "unconnected-(U1B-PCIe_RX_N-Pad118)") (class "Default")
      (node (ref "U1") (pin "118") (pinfunction "PCIe_RX_N_118") (pintype "passive"))
    )
    (net (code "143") (name "unconnected-(U1B-PCIe_RX_P-Pad116)") (class "Default")
      (node (ref "U1") (pin "116") (pinfunction "PCIe_RX_P_116") (pintype "passive"))
    )
    (net (code "144") (name "unconnected-(U1B-PCIe_TX_N-Pad124)") (class "Default")
      (node (ref "U1") (pin "124") (pinfunction "PCIe_TX_N_124") (pintype "passive"))
    )
    (net (code "145") (name "unconnected-(U1B-PCIe_TX_P-Pad122)") (class "Default")
      (node (ref "U1") (pin "122") (pinfunction "PCIe_TX_P_122") (pintype "passive"))
    )
    (net (code "146") (name "unconnected-(U1B-PCIe_nRST-Pad109)") (class "Default")
      (node (ref "U1") (pin "109") (pinfunction "PCIe_nRST_109") (pintype "passive"))
    )
    (net (code "147") (name "unconnected-(U1B-Reserved-Pad104)") (class "Default")
      (node (ref "U1") (pin "104") (pinfunction "Reserved_104") (pintype "passive"))
    )
    (net (code "148") (name "unconnected-(U1B-Reserved-Pad106)") (class "Default")
      (node (ref "U1") (pin "106") (pinfunction "Reserved_106") (pintype "passive"))
    )
    (net (code "149") (name "unconnected-(U1B-VDAC_COMP-Pad111)") (class "Default")
      (node (ref "U1") (pin "111") (pinfunction "VDAC_COMP_111") (pintype "passive"))
    )
  )
)
